# Magnet_Encoder.net
KiCad netlist of a schematic drawn in Altium Designer
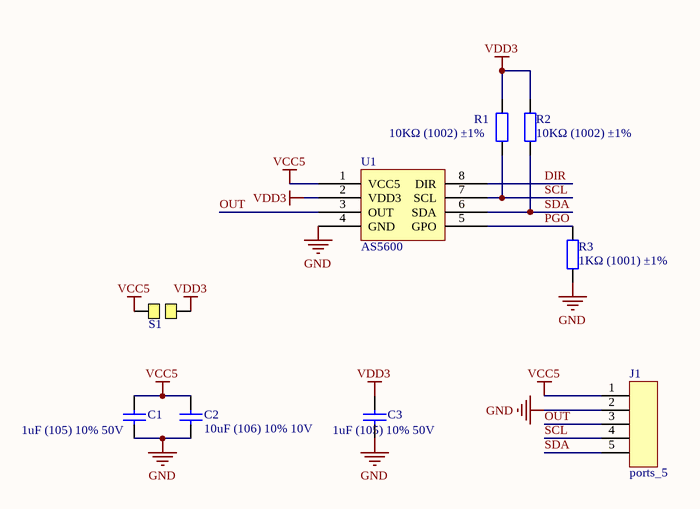
[diagram p0: Magnet_Encoder.SchDoc]

(export (version "E")
  (design (tool "Eeschema 10.0.6"))
  (components
    (comp (ref "C1")
      (value "1uF (105) 10% 50V")
      (footprint "0603_C")
      (description "贴片电容")
      (libsource (lib "Miscellaneous Devices LC") (part "0603 1uF (105) 10% 50V"))
    )
    (comp (ref "C2")
      (value "10uF (106) 10% 10V")
      (footprint "0603_C")
      (description "贴片电容")
      (libsource (lib "Miscellaneous Devices LC") (part "0603 10uF (106) 10% 10V"))
    )
    (comp (ref "C3")
      (value "1uF (105) 10% 50V")
      (footprint "0603_C")
      (description "贴片电容")
      (libsource (lib "Miscellaneous Devices LC") (part "0603 1uF (105) 10% 50V"))
    )
    (comp (ref "J1")
      (value "ports_5")
      (footprint "GH1.25-LS-5P")
      (libsource (lib "my元器件原理图") (part "ports_5"))
    )
    (comp (ref "R1")
      (value "10KΩ (1002) ±1%")
      (footprint "0603_R")
      (description "贴片电阻")
      (libsource (lib "Miscellaneous Devices LC") (part "0603 10KΩ (1002) 1%"))
    )
    (comp (ref "R2")
      (value "10KΩ (1002) ±1%")
      (footprint "0603_R")
      (description "贴片电阻")
      (libsource (lib "Miscellaneous Devices LC") (part "0603 10KΩ (1002) 1%"))
    )
    (comp (ref "R3")
      (value "1KΩ (1001) ±1%")
      (footprint "0603_R")
      (description "贴片电阻")
      (libsource (lib "Miscellaneous Devices LC") (part "0603 1KΩ (1001) 1%"))
    )
    (comp (ref "S1") (value "SHORT-2PIN") (footprint "SHORT-2PIN") (libsource (lib "HY") (part "SHORT-2PIN")))
    (comp (ref "U1")
      (value "AS5600")
      (footprint "SOIC127P600X175-8N")
      (description "Magnet Encoder")
      (libsource (lib "my元器件原理图") (part "AS5600"))
    )
  )
  (nets
    (net (code "1") (name "/DIR") (class "Default")
      (node (ref "U1") (pin "8") (pinfunction "DIR_8") (pintype "passive"))
    )
    (net (code "2") (name "/OUT") (class "Default")
      (node (ref "J1") (pin "3") (pinfunction "3_3") (pintype "passive"))
      (node (ref "U1") (pin "3") (pinfunction "OUT_3") (pintype "passive"))
    )
    (net (code "3") (name "/PGO") (class "Default")
      (node (ref "R3") (pin "2") (pinfunction "2_2") (pintype "passive"))
      (node (ref "U1") (pin "5") (pinfunction "GPO_5") (pintype "passive"))
    )
    (net (code "4") (name "/SCL") (class "Default")
      (node (ref "J1") (pin "4") (pinfunction "4_4") (pintype "passive"))
      (node (ref "R1") (pin "1") (pinfunction "1_1") (pintype "passive"))
      (node (ref "U1") (pin "7") (pinfunction "SCL_7") (pintype "passive"))
    )
    (net (code "5") (name "/SDA") (class "Default")
      (node (ref "J1") (pin "5") (pinfunction "5_5") (pintype "passive"))
      (node (ref "R2") (pin "1") (pinfunction "1_1") (pintype "passive"))
      (node (ref "U1") (pin "6") (pinfunction "SDA_6") (pintype "passive"))
    )
    (net (code "6") (name "GND") (class "Default")
      (node (ref "C1") (pin "1") (pinfunction "1_1") (pintype "passive"))
      (node (ref "C2") (pin "1") (pinfunction "1_1") (pintype "passive"))
      (node (ref "C3") (pin "1") (pinfunction "1_1") (pintype "passive"))
      (node (ref "J1") (pin "2") (pinfunction "2_2") (pintype "passive"))
      (node (ref "R3") (pin "1") (pinfunction "1_1") (pintype "passive"))
      (node (ref "U1") (pin "4") (pinfunction "GND_4") (pintype "passive"))
    )
    (net (code "7") (name "VCC5") (class "Default")
      (node (ref "C1") (pin "2") (pinfunction "2_2") (pintype "passive"))
      (node (ref "C2") (pin "2") (pinfunction "2_2") (pintype "passive"))
      (node (ref "J1") (pin "1") (pinfunction "1_1") (pintype "passive"))
      (node (ref "S1") (pin "1") (pintype "passive"))
      (node (ref "U1") (pin "1") (pinfunction "VCC5_1") (pintype "passive"))
    )
    (net (code "8") (name "VDD3") (class "Default")
      (node (ref "C3") (pin "2") (pinfunction "2_2") (pintype "passive"))
      (node (ref "R1") (pin "2") (pinfunction "2_2") (pintype "passive"))
      (node (ref "R2") (pin "2") (pinfunction "2_2") (pintype "passive"))
      (node (ref "S1") (pin "2") (pintype "passive"))
      (node (ref "U1") (pin "2") (pinfunction "VDD3_2") (pintype "passive"))
    )
  )
)
